# Measuring.net
KiCad netlist of a schematic drawn in Altium Designer
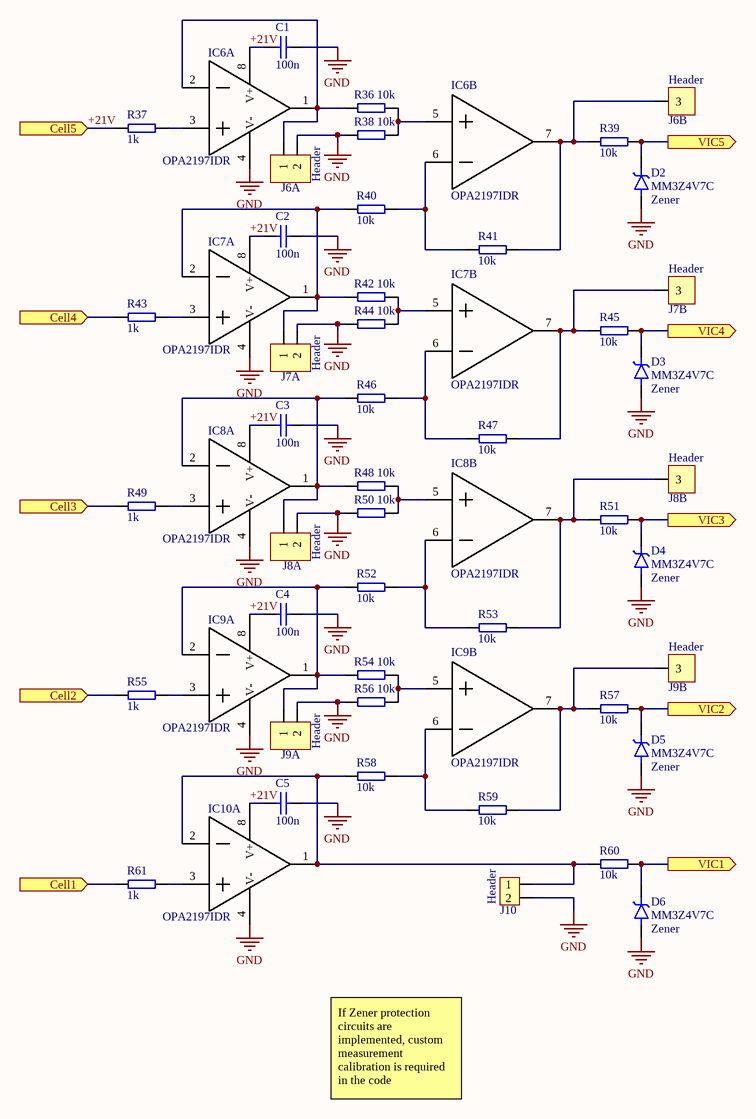
[diagram p0: Measuring.SchDoc]

(export (version "E")
  (design (tool "Eeschema 10.0.6"))
  (components
    (comp (ref "C1")
      (value "100nF_35V")
      (footprint "C_0805")
      (description "Capacitor [SMD]")
      (fields
        (field (name "NAME") "100n")
        (field (name "TOLERANCE") "10%")
        (field (name "MANUFACTURER") "Murata")
      )
      (libsource (lib "PassiveBMS_schlib") (part "C_100nF_0805"))
    )
    (comp (ref "C2")
      (value "100nF_35V")
      (footprint "C_0805")
      (description "Capacitor [SMD]")
      (fields
        (field (name "NAME") "100n")
        (field (name "TOLERANCE") "10%")
        (field (name "MANUFACTURER") "Murata")
      )
      (libsource (lib "PassiveBMS_schlib") (part "C_100nF_0805"))
    )
    (comp (ref "C3")
      (value "100nF_35V")
      (footprint "C_0805")
      (description "Capacitor [SMD]")
      (fields
        (field (name "NAME") "100n")
        (field (name "TOLERANCE") "10%")
        (field (name "MANUFACTURER") "Murata")
      )
      (libsource (lib "PassiveBMS_schlib") (part "C_100nF_0805"))
    )
    (comp (ref "C4")
      (value "100nF_35V")
      (footprint "C_0805")
      (description "Capacitor [SMD]")
      (fields
        (field (name "NAME") "100n")
        (field (name "TOLERANCE") "10%")
        (field (name "MANUFACTURER") "Murata")
      )
      (libsource (lib "PassiveBMS_schlib") (part "C_100nF_0805"))
    )
    (comp (ref "C5")
      (value "100nF_35V")
      (footprint "C_0805")
      (description "Capacitor [SMD]")
      (fields
        (field (name "NAME") "100n")
        (field (name "TOLERANCE") "10%")
        (field (name "MANUFACTURER") "Murata")
      )
      (libsource (lib "PassiveBMS_schlib") (part "C_100nF_0805"))
    )
    (comp (ref "D2")
      (value "MM3Z4V7C")
      (footprint "SODFL2512X90N")
      (description "Zener Single Diode, 4.7 V, 200 mW [SMD]")
      (fields
        (field (name "MP") "1N4148WS")
        (field (name "MF") "ON Semiconductor")
        (field (name "TYPE") "Zener")
      )
      (libsource (lib "PassiveBMS_schlib") (part "MM3Z4V7C_SOD-323F"))
    )
    (comp (ref "D3")
      (value "MM3Z4V7C")
      (footprint "SODFL2512X90N")
      (description "Zener Single Diode, 4.7 V, 200 mW [SMD]")
      (fields
        (field (name "MP") "1N4148WS")
        (field (name "MF") "ON Semiconductor")
        (field (name "TYPE") "Zener")
      )
      (libsource (lib "PassiveBMS_schlib") (part "MM3Z4V7C_SOD-323F"))
    )
    (comp (ref "D4")
      (value "MM3Z4V7C")
      (footprint "SODFL2512X90N")
      (description "Zener Single Diode, 4.7 V, 200 mW [SMD]")
      (fields
        (field (name "MP") "1N4148WS")
        (field (name "MF") "ON Semiconductor")
        (field (name "TYPE") "Zener")
      )
      (libsource (lib "PassiveBMS_schlib") (part "MM3Z4V7C_SOD-323F"))
    )
    (comp (ref "D5")
      (value "MM3Z4V7C")
      (footprint "SODFL2512X90N")
      (description "Zener Single Diode, 4.7 V, 200 mW [SMD]")
      (fields
        (field (name "MP") "1N4148WS")
        (field (name "MF") "ON Semiconductor")
        (field (name "TYPE") "Zener")
      )
      (libsource (lib "PassiveBMS_schlib") (part "MM3Z4V7C_SOD-323F"))
    )
    (comp (ref "D6")
      (value "MM3Z4V7C")
      (footprint "SODFL2512X90N")
      (description "Zener Single Diode, 4.7 V, 200 mW [SMD]")
      (fields
        (field (name "MP") "1N4148WS")
        (field (name "MF") "ON Semiconductor")
        (field (name "TYPE") "Zener")
      )
      (libsource (lib "PassiveBMS_schlib") (part "MM3Z4V7C_SOD-323F"))
    )
    (comp (ref "IC6")
      (value "OPA2197IDR_8-SOIC")
      (footprint "SOIC8")
      (description "Dual OP AMP [TH]")
      (fields
        (field (name "MOUSER PART NUMBER") "595-OPA2197IDR")
        (field (name "MANUFACTURER_PART_NUMBER") "OPA2197IDR")
        (field (name "MANUFACTURER") "Texas Instruments")
      )
      (libsource (lib "PassiveBMS_schlib") (part "OPA2197IDR_8-SOIC"))
    )
    (comp (ref "IC7")
      (value "OPA2197IDR_8-SOIC")
      (footprint "SOIC8")
      (description "Dual OP AMP [TH]")
      (fields
        (field (name "MOUSER PART NUMBER") "595-OPA2197IDR")
        (field (name "MANUFACTURER_PART_NUMBER") "OPA2197IDR")
        (field (name "MANUFACTURER") "Texas Instruments")
      )
      (libsource (lib "PassiveBMS_schlib") (part "OPA2197IDR_8-SOIC"))
    )
    (comp (ref "IC8")
      (value "OPA2197IDR_8-SOIC")
      (footprint "SOIC8")
      (description "Dual OP AMP [TH]")
      (fields
        (field (name "MOUSER PART NUMBER") "595-OPA2197IDR")
        (field (name "MANUFACTURER_PART_NUMBER") "OPA2197IDR")
        (field (name "MANUFACTURER") "Texas Instruments")
      )
      (libsource (lib "PassiveBMS_schlib") (part "OPA2197IDR_8-SOIC"))
    )
    (comp (ref "IC9")
      (value "OPA2197IDR_8-SOIC")
      (footprint "SOIC8")
      (description "Dual OP AMP [TH]")
      (fields
        (field (name "MOUSER PART NUMBER") "595-OPA2197IDR")
        (field (name "MANUFACTURER_PART_NUMBER") "OPA2197IDR")
        (field (name "MANUFACTURER") "Texas Instruments")
      )
      (libsource (lib "PassiveBMS_schlib") (part "OPA2197IDR_8-SOIC"))
    )
    (comp (ref "IC10")
      (value "OPA2197IDR_8-SOIC")
      (footprint "SOIC8")
      (description "Dual OP AMP [TH]")
      (fields
        (field (name "MOUSER PART NUMBER") "595-OPA2197IDR")
        (field (name "MANUFACTURER_PART_NUMBER") "OPA2197IDR")
        (field (name "MANUFACTURER") "Texas Instruments")
      )
      (libsource (lib "PassiveBMS_schlib") (part "OPA2197IDR_8-SOIC"))
    )
    (comp (ref "J6")
      (value "2.54mm pitch")
      (footprint "HDR_1X3_2.54mm-MALE")
      (description "Header, 3-Pin [TH]")
      (fields
        (field (name "MANUFACTURER") "Molex")
        (field (name "MANUFACTURER PART NUMBER") "22-28-4150")
        (field (name "NAME") "Header")
        (field (name "PUBLISHER") "Altium Limited")
      )
      (libsource (lib "PassiveBMS_schlib") (part "Header 1x3AB"))
    )
    (comp (ref "J7")
      (value "2.54mm pitch")
      (footprint "HDR_1X3_2.54mm-MALE")
      (description "Header, 3-Pin [TH]")
      (fields
        (field (name "MANUFACTURER") "Molex")
        (field (name "MANUFACTURER PART NUMBER") "22-28-4150")
        (field (name "NAME") "Header")
        (field (name "PUBLISHER") "Altium Limited")
      )
      (libsource (lib "PassiveBMS_schlib") (part "Header 1x3AB"))
    )
    (comp (ref "J8")
      (value "2.54mm pitch")
      (footprint "HDR_1X3_2.54mm-MALE")
      (description "Header, 3-Pin [TH]")
      (fields
        (field (name "MANUFACTURER") "Molex")
        (field (name "MANUFACTURER PART NUMBER") "22-28-4150")
        (field (name "NAME") "Header")
        (field (name "PUBLISHER") "Altium Limited")
      )
      (libsource (lib "") (part "Header 1x3AB_1"))
    )
    (comp (ref "J9")
      (value "2.54mm pitch")
      (footprint "HDR_1X3_2.54mm-MALE")
      (description "Header, 3-Pin [TH]")
      (fields
        (field (name "MANUFACTURER") "Molex")
        (field (name "MANUFACTURER PART NUMBER") "22-28-4150")
        (field (name "NAME") "Header")
        (field (name "PUBLISHER") "Altium Limited")
      )
      (libsource (lib "") (part "Header 1x3AB_1"))
    )
    (comp (ref "J10")
      (value "2.54mm pitch")
      (footprint "HDR_1x2_2.54mm-MALE")
      (description "Header, 2-Pin [TH]")
      (fields
        (field (name "MANUFACTURER") "Molex")
        (field (name "MANUFACTURER PART NUMBER") "22-28-4150")
        (field (name "NAME") "Header")
        (field (name "PUBLISHER") "Altium Limited")
      )
      (libsource (lib "PassiveBMS_schlib") (part "Header 1x2"))
    )
    (comp (ref "R36")
      (value "10k_125mW")
      (footprint "R_0805")
      (description "Resistor [SMD]")
      (fields
        (field (name "NAME") "10k")
        (field (name "TOLERANCE") "1%")
        (field (name "MANUFACTURER") "Vishay")
      )
      (libsource (lib "PassiveBMS_schlib") (part "R_10k_0805"))
    )
    (comp (ref "R37")
      (value "1k_125mW")
      (footprint "R_0805")
      (description "Resistor [SMD]")
      (fields
        (field (name "NAME") "1k")
        (field (name "TOLERANCE") "1%")
        (field (name "MANUFACTURER") "Vishay")
      )
      (libsource (lib "PassiveBMS_schlib") (part "R_1k_0805"))
    )
    (comp (ref "R38")
      (value "10k_125mW")
      (footprint "R_0805")
      (description "Resistor [SMD]")
      (fields
        (field (name "NAME") "10k")
        (field (name "TOLERANCE") "1%")
        (field (name "MANUFACTURER") "Vishay")
      )
      (libsource (lib "PassiveBMS_schlib") (part "R_10k_0805"))
    )
    (comp (ref "R39")
      (value "10k_125mW")
      (footprint "R_0805")
      (description "Resistor [SMD]")
      (fields
        (field (name "NAME") "10k")
        (field (name "TOLERANCE") "1%")
        (field (name "MANUFACTURER") "Vishay")
      )
      (libsource (lib "PassiveBMS_schlib") (part "R_10k_0805"))
    )
    (comp (ref "R40")
      (value "10k_125mW")
      (footprint "R_0805")
      (description "Resistor [SMD]")
      (fields
        (field (name "NAME") "10k")
        (field (name "TOLERANCE") "1%")
        (field (name "MANUFACTURER") "Vishay")
      )
      (libsource (lib "PassiveBMS_schlib") (part "R_10k_0805"))
    )
    (comp (ref "R41")
      (value "10k_125mW")
      (footprint "R_0805")
      (description "Resistor [SMD]")
      (fields
        (field (name "NAME") "10k")
        (field (name "TOLERANCE") "1%")
        (field (name "MANUFACTURER") "Vishay")
      )
      (libsource (lib "PassiveBMS_schlib") (part "R_10k_0805"))
    )
    (comp (ref "R42")
      (value "10k_125mW")
      (footprint "R_0805")
      (description "Resistor [SMD]")
      (fields
        (field (name "NAME") "10k")
        (field (name "TOLERANCE") "1%")
        (field (name "MANUFACTURER") "Vishay")
      )
      (libsource (lib "PassiveBMS_schlib") (part "R_10k_0805"))
    )
    (comp (ref "R43")
      (value "1k_125mW")
      (footprint "R_0805")
      (description "Resistor [SMD]")
      (fields
        (field (name "NAME") "1k")
        (field (name "TOLERANCE") "1%")
        (field (name "MANUFACTURER") "Vishay")
      )
      (libsource (lib "PassiveBMS_schlib") (part "R_1k_0805"))
    )
    (comp (ref "R44")
      (value "10k_125mW")
      (footprint "R_0805")
      (description "Resistor [SMD]")
      (fields
        (field (name "NAME") "10k")
        (field (name "TOLERANCE") "1%")
        (field (name "MANUFACTURER") "Vishay")
      )
      (libsource (lib "PassiveBMS_schlib") (part "R_10k_0805"))
    )
    (comp (ref "R45")
      (value "10k_125mW")
      (footprint "R_0805")
      (description "Resistor [SMD]")
      (fields
        (field (name "NAME") "10k")
        (field (name "TOLERANCE") "1%")
        (field (name "MANUFACTURER") "Vishay")
      )
      (libsource (lib "PassiveBMS_schlib") (part "R_10k_0805"))
    )
    (comp (ref "R46")
      (value "10k_125mW")
      (footprint "R_0805")
      (description "Resistor [SMD]")
      (fields
        (field (name "NAME") "10k")
        (field (name "TOLERANCE") "1%")
        (field (name "MANUFACTURER") "Vishay")
      )
      (libsource (lib "PassiveBMS_schlib") (part "R_10k_0805"))
    )
    (comp (ref "R47")
      (value "10k_125mW")
      (footprint "R_0805")
      (description "Resistor [SMD]")
      (fields
        (field (name "NAME") "10k")
        (field (name "TOLERANCE") "1%")
        (field (name "MANUFACTURER") "Vishay")
      )
      (libsource (lib "PassiveBMS_schlib") (part "R_10k_0805"))
    )
    (comp (ref "R48")
      (value "10k_125mW")
      (footprint "R_0805")
      (description "Resistor [SMD]")
      (fields
        (field (name "NAME") "10k")
        (field (name "TOLERANCE") "1%")
        (field (name "MANUFACTURER") "Vishay")
      )
      (libsource (lib "PassiveBMS_schlib") (part "R_10k_0805"))
    )
    (comp (ref "R49")
      (value "1k_125mW")
      (footprint "R_0805")
      (description "Resistor [SMD]")
      (fields
        (field (name "NAME") "1k")
        (field (name "TOLERANCE") "1%")
        (field (name "MANUFACTURER") "Vishay")
      )
      (libsource (lib "PassiveBMS_schlib") (part "R_1k_0805"))
    )
    (comp (ref "R50")
      (value "10k_125mW")
      (footprint "R_0805")
      (description "Resistor [SMD]")
      (fields
        (field (name "NAME") "10k")
        (field (name "TOLERANCE") "1%")
        (field (name "MANUFACTURER") "Vishay")
      )
      (libsource (lib "PassiveBMS_schlib") (part "R_10k_0805"))
    )
    (comp (ref "R51")
      (value "10k_125mW")
      (footprint "R_0805")
      (description "Resistor [SMD]")
      (fields
        (field (name "NAME") "10k")
        (field (name "TOLERANCE") "1%")
        (field (name "MANUFACTURER") "Vishay")
      )
      (libsource (lib "PassiveBMS_schlib") (part "R_10k_0805"))
    )
    (comp (ref "R52")
      (value "10k_125mW")
      (footprint "R_0805")
      (description "Resistor [SMD]")
      (fields
        (field (name "NAME") "10k")
        (field (name "TOLERANCE") "1%")
        (field (name "MANUFACTURER") "Vishay")
      )
      (libsource (lib "PassiveBMS_schlib") (part "R_10k_0805"))
    )
    (comp (ref "R53")
      (value "10k_125mW")
      (footprint "R_0805")
      (description "Resistor [SMD]")
      (fields
        (field (name "NAME") "10k")
        (field (name "TOLERANCE") "1%")
        (field (name "MANUFACTURER") "Vishay")
      )
      (libsource (lib "PassiveBMS_schlib") (part "R_10k_0805"))
    )
    (comp (ref "R54")
      (value "10k_125mW")
      (footprint "R_0805")
      (description "Resistor [SMD]")
      (fields
        (field (name "NAME") "10k")
        (field (name "TOLERANCE") "1%")
        (field (name "MANUFACTURER") "Vishay")
      )
      (libsource (lib "PassiveBMS_schlib") (part "R_10k_0805"))
    )
    (comp (ref "R55")
      (value "1k_125mW")
      (footprint "R_0805")
      (description "Resistor [SMD]")
      (fields
        (field (name "NAME") "1k")
        (field (name "TOLERANCE") "1%")
        (field (name "MANUFACTURER") "Vishay")
      )
      (libsource (lib "PassiveBMS_schlib") (part "R_1k_0805"))
    )
    (comp (ref "R56")
      (value "10k_125mW")
      (footprint "R_0805")
      (description "Resistor [SMD]")
      (fields
        (field (name "NAME") "10k")
        (field (name "TOLERANCE") "1%")
        (field (name "MANUFACTURER") "Vishay")
      )
      (libsource (lib "PassiveBMS_schlib") (part "R_10k_0805"))
    )
    (comp (ref "R57")
      (value "10k_125mW")
      (footprint "R_0805")
      (description "Resistor [SMD]")
      (fields
        (field (name "NAME") "10k")
        (field (name "TOLERANCE") "1%")
        (field (name "MANUFACTURER") "Vishay")
      )
      (libsource (lib "PassiveBMS_schlib") (part "R_10k_0805"))
    )
    (comp (ref "R58")
      (value "10k_125mW")
      (footprint "R_0805")
      (description "Resistor [SMD]")
      (fields
        (field (name "NAME") "10k")
        (field (name "TOLERANCE") "1%")
        (field (name "MANUFACTURER") "Vishay")
      )
      (libsource (lib "PassiveBMS_schlib") (part "R_10k_0805"))
    )
    (comp (ref "R59")
      (value "10k_125mW")
      (footprint "R_0805")
      (description "Resistor [SMD]")
      (fields
        (field (name "NAME") "10k")
        (field (name "TOLERANCE") "1%")
        (field (name "MANUFACTURER") "Vishay")
      )
      (libsource (lib "PassiveBMS_schlib") (part "R_10k_0805"))
    )
    (comp (ref "R60")
      (value "10k_125mW")
      (footprint "R_0805")
      (description "Resistor [SMD]")
      (fields
        (field (name "NAME") "10k")
        (field (name "TOLERANCE") "1%")
        (field (name "MANUFACTURER") "Vishay")
      )
      (libsource (lib "PassiveBMS_schlib") (part "R_10k_0805"))
    )
    (comp (ref "R61")
      (value "1k_125mW")
      (footprint "R_0805")
      (description "Resistor [SMD]")
      (fields
        (field (name "NAME") "1k")
        (field (name "TOLERANCE") "1%")
        (field (name "MANUFACTURER") "Vishay")
      )
      (libsource (lib "PassiveBMS_schlib") (part "R_1k_0805"))
    )
  )
  (nets
    (net (code "1") (name "/+21V") (class "Default")
      (node (ref "C1") (pin "2") (pinfunction "2_2") (pintype "passive"))
      (node (ref "C2") (pin "2") (pinfunction "2_2") (pintype "passive"))
      (node (ref "C3") (pin "2") (pinfunction "2_2") (pintype "passive"))
      (node (ref "C4") (pin "2") (pinfunction "2_2") (pintype "passive"))
      (node (ref "C5") (pin "2") (pinfunction "2_2") (pintype "passive"))
      (node (ref "IC10") (pin "8") (pinfunction "V+_8") (pintype "passive"))
      (node (ref "IC6") (pin "8") (pinfunction "V+_8") (pintype "passive"))
      (node (ref "IC7") (pin "8") (pinfunction "V+_8") (pintype "passive"))
      (node (ref "IC8") (pin "8") (pinfunction "V+_8") (pintype "passive"))
      (node (ref "IC9") (pin "8") (pinfunction "V+_8") (pintype "passive"))
      (node (ref "R37") (pin "2") (pinfunction "2_2") (pintype "passive"))
    )
    (net (code "2") (name "/Cell1") (class "Default")
      (node (ref "R61") (pin "2") (pinfunction "2_2") (pintype "passive"))
    )
    (net (code "3") (name "/Cell2") (class "Default")
      (node (ref "R55") (pin "2") (pinfunction "2_2") (pintype "passive"))
    )
    (net (code "4") (name "/Cell3") (class "Default")
      (node (ref "R49") (pin "2") (pinfunction "2_2") (pintype "passive"))
    )
    (net (code "5") (name "/Cell4") (class "Default")
      (node (ref "R43") (pin "2") (pinfunction "2_2") (pintype "passive"))
    )
    (net (code "6") (name "/VIC1") (class "Default")
      (node (ref "D6") (pin "K") (pinfunction "K_K") (pintype "passive"))
      (node (ref "R60") (pin "1") (pinfunction "1_1") (pintype "passive"))
    )
    (net (code "7") (name "/VIC2") (class "Default")
      (node (ref "D5") (pin "K") (pinfunction "K_K") (pintype "passive"))
      (node (ref "R57") (pin "1") (pinfunction "1_1") (pintype "passive"))
    )
    (net (code "8") (name "/VIC3") (class "Default")
      (node (ref "D4") (pin "K") (pinfunction "K_K") (pintype "passive"))
      (node (ref "R51") (pin "1") (pinfunction "1_1") (pintype "passive"))
    )
    (net (code "9") (name "/VIC4") (class "Default")
      (node (ref "D3") (pin "K") (pinfunction "K_K") (pintype "passive"))
      (node (ref "R45") (pin "1") (pinfunction "1_1") (pintype "passive"))
    )
    (net (code "10") (name "/VIC5") (class "Default")
      (node (ref "D2") (pin "K") (pinfunction "K_K") (pintype "passive"))
      (node (ref "R39") (pin "1") (pinfunction "1_1") (pintype "passive"))
    )
    (net (code "11") (name "GND") (class "Default")
      (node (ref "C1") (pin "1") (pinfunction "1_1") (pintype "passive"))
      (node (ref "C2") (pin "1") (pinfunction "1_1") (pintype "passive"))
      (node (ref "C3") (pin "1") (pinfunction "1_1") (pintype "passive"))
      (node (ref "C4") (pin "1") (pinfunction "1_1") (pintype "passive"))
      (node (ref "C5") (pin "1") (pinfunction "1_1") (pintype "passive"))
      (node (ref "D2") (pin "A") (pinfunction "A_A") (pintype "passive"))
      (node (ref "D3") (pin "A") (pinfunction "A_A") (pintype "passive"))
      (node (ref "D4") (pin "A") (pinfunction "A_A") (pintype "passive"))
      (node (ref "D5") (pin "A") (pinfunction "A_A") (pintype "passive"))
      (node (ref "D6") (pin "A") (pinfunction "A_A") (pintype "passive"))
      (node (ref "IC10") (pin "4") (pinfunction "V-_4") (pintype "passive"))
      (node (ref "IC6") (pin "4") (pinfunction "V-_4") (pintype "passive"))
      (node (ref "IC7") (pin "4") (pinfunction "V-_4") (pintype "passive"))
      (node (ref "IC8") (pin "4") (pinfunction "V-_4") (pintype "passive"))
      (node (ref "IC9") (pin "4") (pinfunction "V-_4") (pintype "passive"))
      (node (ref "J10") (pin "2") (pinfunction "2_2") (pintype "passive"))
      (node (ref "J6") (pin "2") (pinfunction "2_2") (pintype "passive"))
      (node (ref "J7") (pin "2") (pinfunction "2_2") (pintype "passive"))
      (node (ref "J8") (pin "2") (pinfunction "2_2") (pintype "passive"))
      (node (ref "J9") (pin "2") (pinfunction "2_2") (pintype "passive"))
      (node (ref "R38") (pin "2") (pinfunction "2_2") (pintype "passive"))
      (node (ref "R44") (pin "2") (pinfunction "2_2") (pintype "passive"))
      (node (ref "R50") (pin "2") (pinfunction "2_2") (pintype "passive"))
      (node (ref "R56") (pin "2") (pinfunction "2_2") (pintype "passive"))
    )
    (net (code "12") (name "Net-(IC6A-+IN_A)") (class "Default")
      (node (ref "IC6") (pin "3") (pinfunction "+IN_A_3") (pintype "passive"))
      (node (ref "R37") (pin "1") (pinfunction "1_1") (pintype "passive"))
    )
    (net (code "13") (name "Net-(IC6A--IN_A)") (class "Default")
      (node (ref "IC6") (pin "1") (pinfunction "OUT_A_1") (pintype "passive"))
      (node (ref "IC6") (pin "2") (pinfunction "-IN_A_2") (pintype "passive"))
      (node (ref "J6") (pin "1") (pinfunction "1_1") (pintype "passive"))
      (node (ref "R36") (pin "2") (pinfunction "2_2") (pintype "passive"))
    )
    (net (code "14") (name "Net-(IC6B-+IN_B)") (class "Default")
      (node (ref "IC6") (pin "5") (pinfunction "+IN_B_5") (pintype "passive"))
      (node (ref "R36") (pin "1") (pinfunction "1_1") (pintype "passive"))
      (node (ref "R38") (pin "1") (pinfunction "1_1") (pintype "passive"))
    )
    (net (code "15") (name "Net-(IC6B--IN_B)") (class "Default")
      (node (ref "IC6") (pin "6") (pinfunction "-IN_B_6") (pintype "passive"))
      (node (ref "R40") (pin "1") (pinfunction "1_1") (pintype "passive"))
      (node (ref "R41") (pin "2") (pinfunction "2_2") (pintype "passive"))
    )
    (net (code "16") (name "Net-(IC6B-OUT_B)") (class "Default")
      (node (ref "IC6") (pin "7") (pinfunction "OUT_B_7") (pintype "passive"))
      (node (ref "J6") (pin "3") (pinfunction "3_3") (pintype "passive"))
      (node (ref "R39") (pin "2") (pinfunction "2_2") (pintype "passive"))
      (node (ref "R41") (pin "1") (pinfunction "1_1") (pintype "passive"))
    )
    (net (code "17") (name "Net-(IC7A-+IN_A)") (class "Default")
      (node (ref "IC7") (pin "3") (pinfunction "+IN_A_3") (pintype "passive"))
      (node (ref "R43") (pin "1") (pinfunction "1_1") (pintype "passive"))
    )
    (net (code "18") (name "Net-(IC7A--IN_A)") (class "Default")
      (node (ref "IC7") (pin "1") (pinfunction "OUT_A_1") (pintype "passive"))
      (node (ref "IC7") (pin "2") (pinfunction "-IN_A_2") (pintype "passive"))
      (node (ref "J7") (pin "1") (pinfunction "1_1") (pintype "passive"))
      (node (ref "R40") (pin "2") (pinfunction "2_2") (pintype "passive"))
      (node (ref "R42") (pin "2") (pinfunction "2_2") (pintype "passive"))
    )
    (net (code "19") (name "Net-(IC7B-+IN_B)") (class "Default")
      (node (ref "IC7") (pin "5") (pinfunction "+IN_B_5") (pintype "passive"))
      (node (ref "R42") (pin "1") (pinfunction "1_1") (pintype "passive"))
      (node (ref "R44") (pin "1") (pinfunction "1_1") (pintype "passive"))
    )
    (net (code "20") (name "Net-(IC7B--IN_B)") (class "Default")
      (node (ref "IC7") (pin "6") (pinfunction "-IN_B_6") (pintype "passive"))
      (node (ref "R46") (pin "1") (pinfunction "1_1") (pintype "passive"))
      (node (ref "R47") (pin "2") (pinfunction "2_2") (pintype "passive"))
    )
    (net (code "21") (name "Net-(IC7B-OUT_B)") (class "Default")
      (node (ref "IC7") (pin "7") (pinfunction "OUT_B_7") (pintype "passive"))
      (node (ref "J7") (pin "3") (pinfunction "3_3") (pintype "passive"))
      (node (ref "R45") (pin "2") (pinfunction "2_2") (pintype "passive"))
      (node (ref "R47") (pin "1") (pinfunction "1_1") (pintype "passive"))
    )
    (net (code "22") (name "Net-(IC8A-+IN_A)") (class "Default")
      (node (ref "IC8") (pin "3") (pinfunction "+IN_A_3") (pintype "passive"))
      (node (ref "R49") (pin "1") (pinfunction "1_1") (pintype "passive"))
    )
    (net (code "23") (name "Net-(IC8A--IN_A)") (class "Default")
      (node (ref "IC8") (pin "1") (pinfunction "OUT_A_1") (pintype "passive"))
      (node (ref "IC8") (pin "2") (pinfunction "-IN_A_2") (pintype "passive"))
      (node (ref "J8") (pin "1") (pinfunction "1_1") (pintype "passive"))
      (node (ref "R46") (pin "2") (pinfunction "2_2") (pintype "passive"))
      (node (ref "R48") (pin "2") (pinfunction "2_2") (pintype "passive"))
    )
    (net (code "24") (name "Net-(IC8B-+IN_B)") (class "Default")
      (node (ref "IC8") (pin "5") (pinfunction "+IN_B_5") (pintype "passive"))
      (node (ref "R48") (pin "1") (pinfunction "1_1") (pintype "passive"))
      (node (ref "R50") (pin "1") (pinfunction "1_1") (pintype "passive"))
    )
    (net (code "25") (name "Net-(IC8B--IN_B)") (class "Default")
      (node (ref "IC8") (pin "6") (pinfunction "-IN_B_6") (pintype "passive"))
      (node (ref "R52") (pin "1") (pinfunction "1_1") (pintype "passive"))
      (node (ref "R53") (pin "2") (pinfunction "2_2") (pintype "passive"))
    )
    (net (code "26") (name "Net-(IC8B-OUT_B)") (class "Default")
      (node (ref "IC8") (pin "7") (pinfunction "OUT_B_7") (pintype "passive"))
      (node (ref "J8") (pin "3") (pinfunction "3_3") (pintype "passive"))
      (node (ref "R51") (pin "2") (pinfunction "2_2") (pintype "passive"))
      (node (ref "R53") (pin "1") (pinfunction "1_1") (pintype "passive"))
    )
    (net (code "27") (name "Net-(IC9A-+IN_A)") (class "Default")
      (node (ref "IC9") (pin "3") (pinfunction "+IN_A_3") (pintype "passive"))
      (node (ref "R55") (pin "1") (pinfunction "1_1") (pintype "passive"))
    )
    (net (code "28") (name "Net-(IC9A--IN_A)") (class "Default")
      (node (ref "IC9") (pin "1") (pinfunction "OUT_A_1") (pintype "passive"))
      (node (ref "IC9") (pin "2") (pinfunction "-IN_A_2") (pintype "passive"))
      (node (ref "J9") (pin "1") (pinfunction "1_1") (pintype "passive"))
      (node (ref "R52") (pin "2") (pinfunction "2_2") (pintype "passive"))
      (node (ref "R54") (pin "2") (pinfunction "2_2") (pintype "passive"))
    )
    (net (code "29") (name "Net-(IC9B-+IN_B)") (class "Default")
      (node (ref "IC9") (pin "5") (pinfunction "+IN_B_5") (pintype "passive"))
      (node (ref "R54") (pin "1") (pinfunction "1_1") (pintype "passive"))
      (node (ref "R56") (pin "1") (pinfunction "1_1") (pintype "passive"))
    )
    (net (code "30") (name "Net-(IC9B--IN_B)") (class "Default")
      (node (ref "IC9") (pin "6") (pinfunction "-IN_B_6") (pintype "passive"))
      (node (ref "R58") (pin "1") (pinfunction "1_1") (pintype "passive"))
      (node (ref "R59") (pin "2") (pinfunction "2_2") (pintype "passive"))
    )
    (net (code "31") (name "Net-(IC9B-OUT_B)") (class "Default")
      (node (ref "IC9") (pin "7") (pinfunction "OUT_B_7") (pintype "passive"))
      (node (ref "J9") (pin "3") (pinfunction "3_3") (pintype "passive"))
      (node (ref "R57") (pin "2") (pinfunction "2_2") (pintype "passive"))
      (node (ref "R59") (pin "1") (pinfunction "1_1") (pintype "passive"))
    )
    (net (code "32") (name "Net-(IC10A-+IN_A)") (class "Default")
      (node (ref "IC10") (pin "3") (pinfunction "+IN_A_3") (pintype "passive"))
      (node (ref "R61") (pin "1") (pinfunction "1_1") (pintype "passive"))
    )
    (net (code "33") (name "Net-(IC10A--IN_A)") (class "Default")
      (node (ref "IC10") (pin "1") (pinfunction "OUT_A_1") (pintype "passive"))
      (node (ref "IC10") (pin "2") (pinfunction "-IN_A_2") (pintype "passive"))
      (node (ref "J10") (pin "1") (pinfunction "1_1") (pintype "passive"))
      (node (ref "R58") (pin "2") (pinfunction "2_2") (pintype "passive"))
      (node (ref "R60") (pin "2") (pinfunction "2_2") (pintype "passive"))
    )
  )
)
